# Auto2017.net
KiCad netlist of a schematic drawn in EAGLE
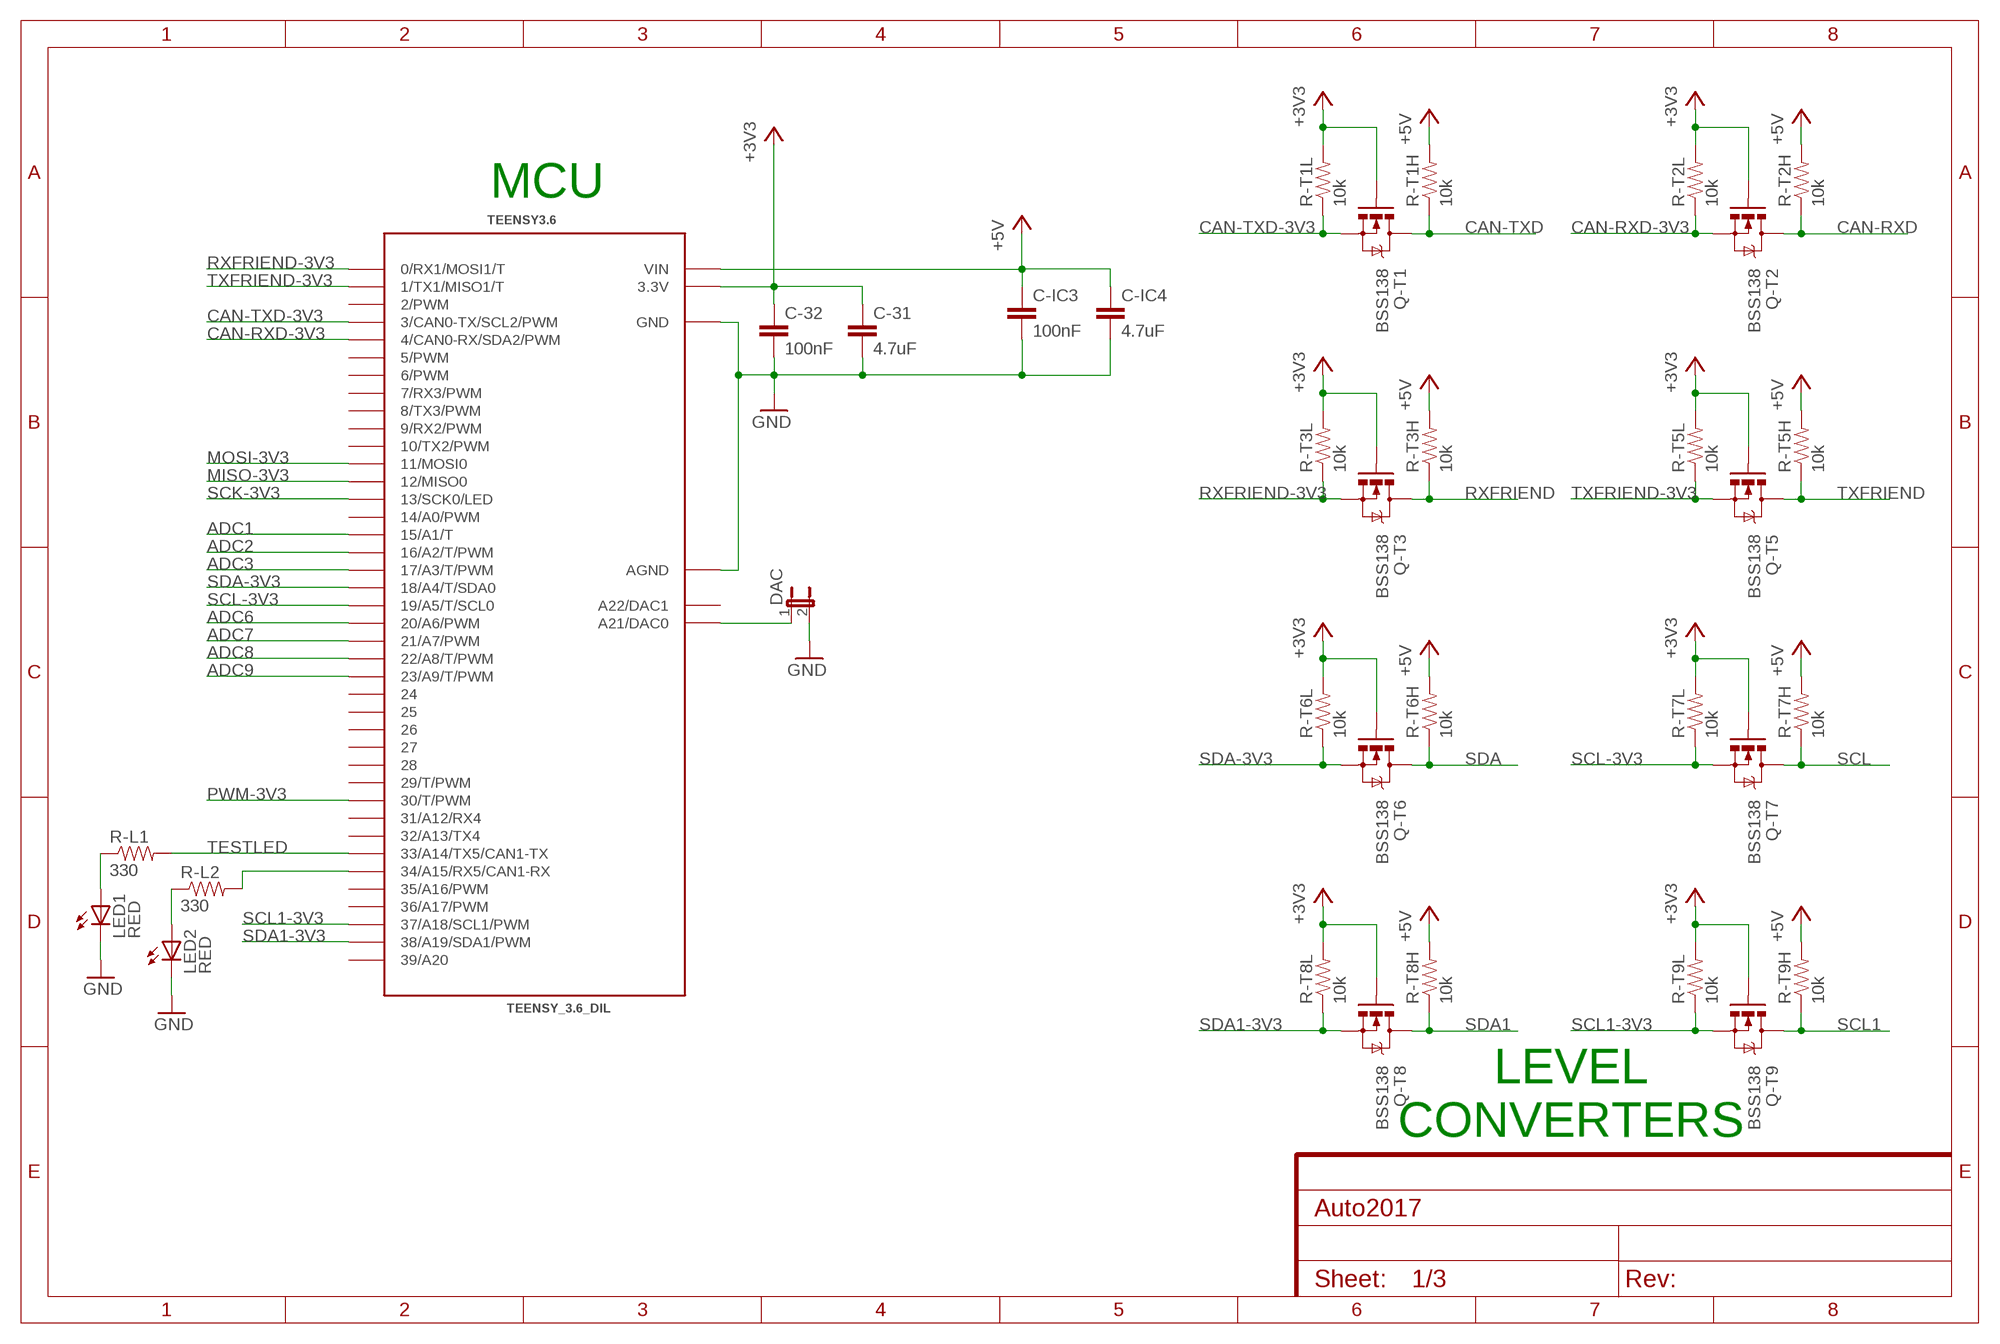
[diagram p0: schematic, sheet 1]
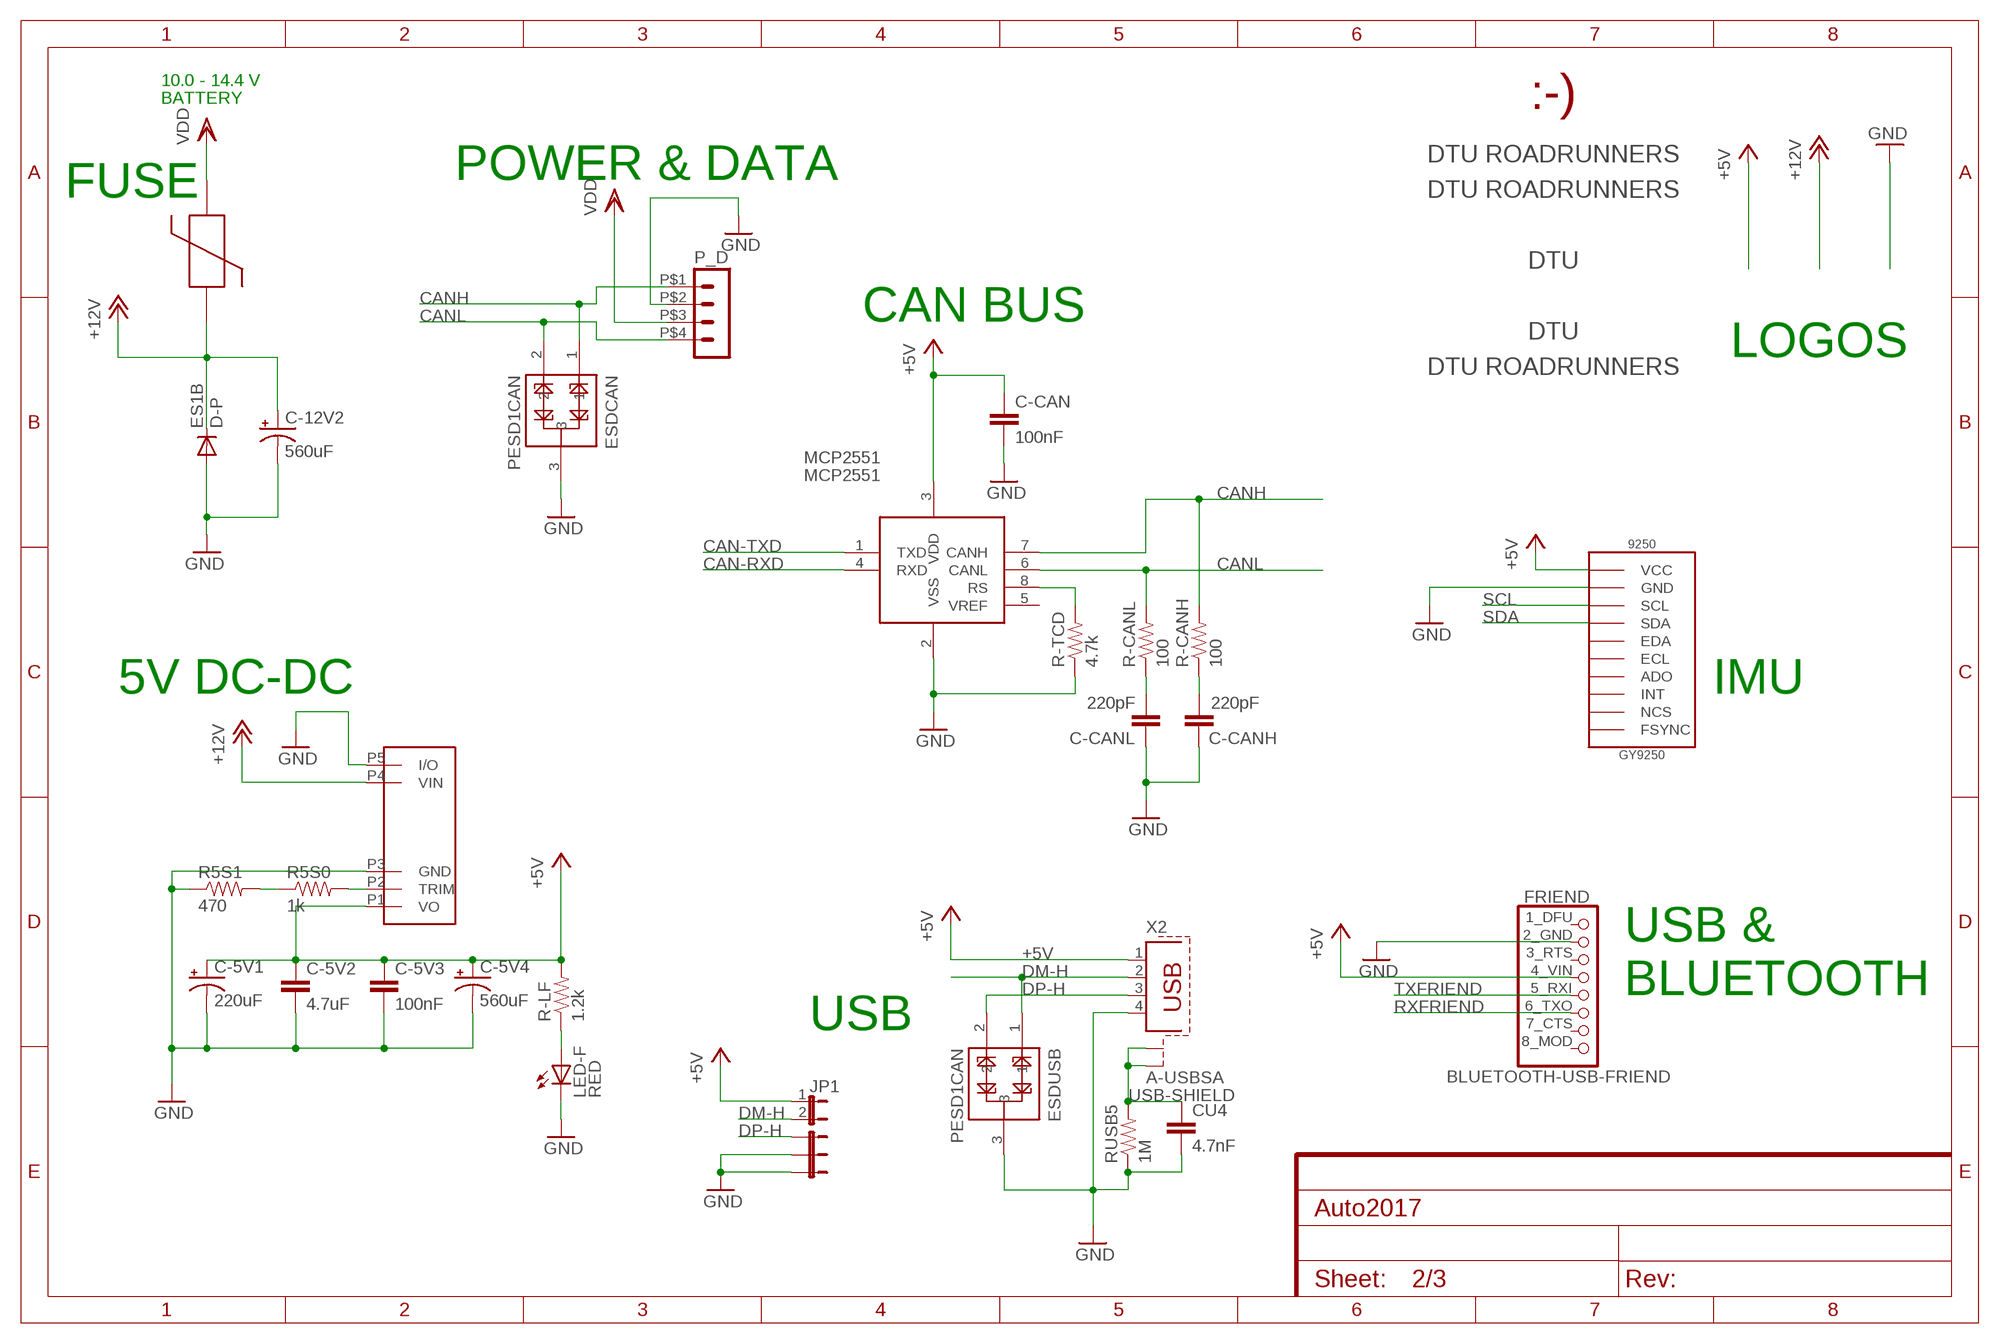
[diagram p1: schematic, sheet 2]
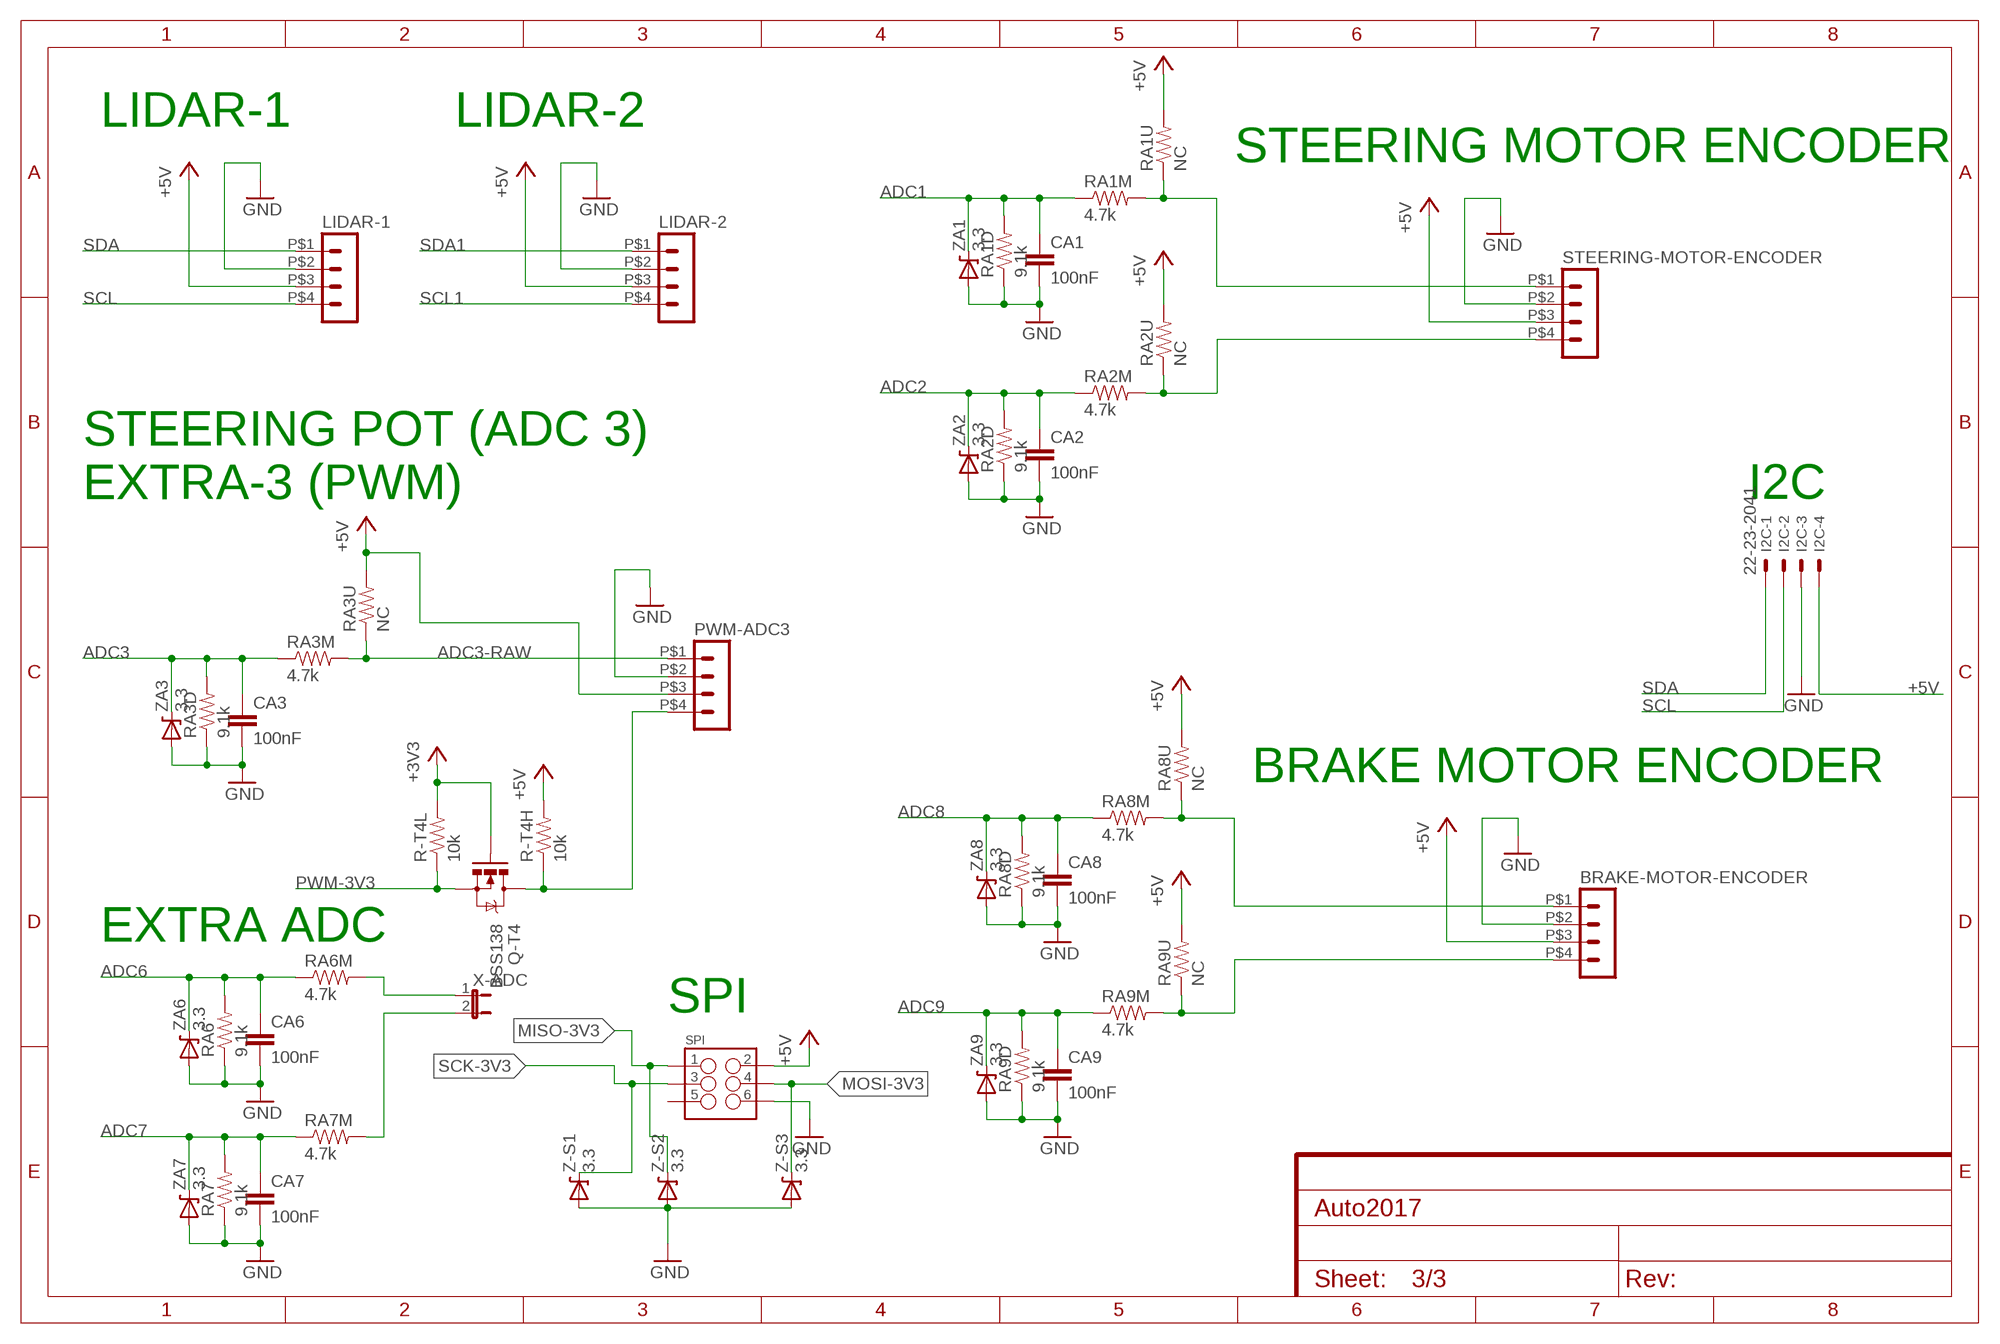
[diagram p2: schematic, sheet 3]

(export (version "E")
  (design (tool "Eeschema 10.0.6"))
  (components
    (comp (ref "BRAKE-MOTOR-ENCODER")
      (value "HEADER_POS4_43045-0401")
      (footprint "eagle-import:43045-0400")
      (libsource (lib "eagle-import") (part "HEADER_POS4_?43045-0401"))
    )
    (comp (ref "CA1")
      (value "100nF")
      (footprint "eagle-import:0805")
      (libsource (lib "eagle-import") (part "CAP0805"))
    )
    (comp (ref "CA2")
      (value "100nF")
      (footprint "eagle-import:0805")
      (libsource (lib "eagle-import") (part "CAP0805"))
    )
    (comp (ref "CA3")
      (value "100nF")
      (footprint "eagle-import:0805")
      (libsource (lib "eagle-import") (part "CAP0805"))
    )
    (comp (ref "CA6")
      (value "100nF")
      (footprint "eagle-import:0805")
      (libsource (lib "eagle-import") (part "CAP0805"))
    )
    (comp (ref "CA7")
      (value "100nF")
      (footprint "eagle-import:0805")
      (libsource (lib "eagle-import") (part "CAP0805"))
    )
    (comp (ref "CA8")
      (value "100nF")
      (footprint "eagle-import:0805")
      (libsource (lib "eagle-import") (part "CAP0805"))
    )
    (comp (ref "CA9")
      (value "100nF")
      (footprint "eagle-import:0805")
      (libsource (lib "eagle-import") (part "CAP0805"))
    )
    (comp (ref "I2C")
      (value "22-23-2041")
      (footprint "eagle-import:22-23-2041")
      (fields (field (name "MF") "MOLEX"))
      (libsource (lib "eagle-import") (part "22-23-2041"))
    )
    (comp (ref "LIDAR-1")
      (value "HEADER_POS4_43045-0401")
      (footprint "eagle-import:43045-0400")
      (libsource (lib "eagle-import") (part "HEADER_POS4_?43045-0401"))
    )
    (comp (ref "LIDAR-2")
      (value "HEADER_POS4_43045-0401")
      (footprint "eagle-import:43045-0400")
      (libsource (lib "eagle-import") (part "HEADER_POS4_?43045-0401"))
    )
    (comp (ref "PWM-ADC3")
      (value "HEADER_POS4_43045-0401")
      (footprint "eagle-import:43045-0400")
      (libsource (lib "eagle-import") (part "HEADER_POS4_?43045-0401"))
    )
    (comp (ref "Q-T4")
      (value "BSS138")
      (footprint "eagle-import:SOT23-3")
      (libsource (lib "eagle-import") (part "MOSFET-NCHANNELBSS123LT1G"))
    )
    (comp (ref "R-T4H")
      (value "10k")
      (footprint "eagle-import:0805")
      (libsource (lib "eagle-import") (part "RESISTOR0805-RES"))
    )
    (comp (ref "R-T4L")
      (value "10k")
      (footprint "eagle-import:0805")
      (libsource (lib "eagle-import") (part "RESISTOR0805-RES"))
    )
    (comp (ref "RA1D")
      (value "9.1k")
      (footprint "eagle-import:0805")
      (libsource (lib "eagle-import") (part "RESISTOR0805-RES"))
    )
    (comp (ref "RA1M")
      (value "4.7k")
      (footprint "eagle-import:0805")
      (libsource (lib "eagle-import") (part "RESISTOR0805-RES"))
    )
    (comp (ref "RA1U")
      (value "NC")
      (footprint "eagle-import:0805")
      (libsource (lib "eagle-import") (part "RESISTOR0805-RES"))
    )
    (comp (ref "RA2D")
      (value "9.1k")
      (footprint "eagle-import:0805")
      (libsource (lib "eagle-import") (part "RESISTOR0805-RES"))
    )
    (comp (ref "RA2M")
      (value "4.7k")
      (footprint "eagle-import:0805")
      (libsource (lib "eagle-import") (part "RESISTOR0805-RES"))
    )
    (comp (ref "RA2U")
      (value "NC")
      (footprint "eagle-import:0805")
      (libsource (lib "eagle-import") (part "RESISTOR0805-RES"))
    )
    (comp (ref "RA3D")
      (value "9.1k")
      (footprint "eagle-import:0805")
      (libsource (lib "eagle-import") (part "RESISTOR0805-RES"))
    )
    (comp (ref "RA3M")
      (value "4.7k")
      (footprint "eagle-import:0805")
      (libsource (lib "eagle-import") (part "RESISTOR0805-RES"))
    )
    (comp (ref "RA3U")
      (value "NC")
      (footprint "eagle-import:0805")
      (libsource (lib "eagle-import") (part "RESISTOR0805-RES"))
    )
    (comp (ref "RA6")
      (value "9.1k")
      (footprint "eagle-import:0805")
      (libsource (lib "eagle-import") (part "RESISTOR0805-RES"))
    )
    (comp (ref "RA6M")
      (value "4.7k")
      (footprint "eagle-import:0805")
      (libsource (lib "eagle-import") (part "RESISTOR0805-RES"))
    )
    (comp (ref "RA7")
      (value "9.1k")
      (footprint "eagle-import:0805")
      (libsource (lib "eagle-import") (part "RESISTOR0805-RES"))
    )
    (comp (ref "RA7M")
      (value "4.7k")
      (footprint "eagle-import:0805")
      (libsource (lib "eagle-import") (part "RESISTOR0805-RES"))
    )
    (comp (ref "RA8D")
      (value "9.1k")
      (footprint "eagle-import:0805")
      (libsource (lib "eagle-import") (part "RESISTOR0805-RES"))
    )
    (comp (ref "RA8M")
      (value "4.7k")
      (footprint "eagle-import:0805")
      (libsource (lib "eagle-import") (part "RESISTOR0805-RES"))
    )
    (comp (ref "RA8U")
      (value "NC")
      (footprint "eagle-import:0805")
      (libsource (lib "eagle-import") (part "RESISTOR0805-RES"))
    )
    (comp (ref "RA9D")
      (value "9.1k")
      (footprint "eagle-import:0805")
      (libsource (lib "eagle-import") (part "RESISTOR0805-RES"))
    )
    (comp (ref "RA9M")
      (value "4.7k")
      (footprint "eagle-import:0805")
      (libsource (lib "eagle-import") (part "RESISTOR0805-RES"))
    )
    (comp (ref "RA9U")
      (value "NC")
      (footprint "eagle-import:0805")
      (libsource (lib "eagle-import") (part "RESISTOR0805-RES"))
    )
    (comp (ref "SPI")
      (value "M03X2POGO_PINS")
      (footprint "eagle-import:2X3_POGO")
      (libsource (lib "eagle-import") (part "M03X2POGO_PINS"))
    )
    (comp (ref "STEERING-MOTOR-ENCODER")
      (value "HEADER_POS4_43045-0401")
      (footprint "eagle-import:43045-0400")
      (libsource (lib "eagle-import") (part "HEADER_POS4_?43045-0401"))
    )
    (comp (ref "X-ADC")
      (value "JUMPER-2PTH")
      (footprint "eagle-import:1X02")
      (libsource (lib "eagle-import") (part "JUMPER-2PTH"))
    )
    (comp (ref "Z-S1")
      (value "3.3")
      (footprint "eagle-import:SOD123")
      (libsource (lib "eagle-import") (part "ZENER"))
    )
    (comp (ref "Z-S2")
      (value "3.3")
      (footprint "eagle-import:SOD123")
      (libsource (lib "eagle-import") (part "ZENER"))
    )
    (comp (ref "Z-S3")
      (value "3.3")
      (footprint "eagle-import:SOD123")
      (libsource (lib "eagle-import") (part "ZENER"))
    )
    (comp (ref "ZA1")
      (value "3.3")
      (footprint "eagle-import:SOD123")
      (libsource (lib "eagle-import") (part "ZENER"))
    )
    (comp (ref "ZA2")
      (value "3.3")
      (footprint "eagle-import:SOD123")
      (libsource (lib "eagle-import") (part "ZENER"))
    )
    (comp (ref "ZA3")
      (value "3.3")
      (footprint "eagle-import:SOD123")
      (libsource (lib "eagle-import") (part "ZENER"))
    )
    (comp (ref "ZA6")
      (value "3.3")
      (footprint "eagle-import:SOD123")
      (libsource (lib "eagle-import") (part "ZENER"))
    )
    (comp (ref "ZA7")
      (value "3.3")
      (footprint "eagle-import:SOD123")
      (libsource (lib "eagle-import") (part "ZENER"))
    )
    (comp (ref "ZA8")
      (value "3.3")
      (footprint "eagle-import:SOD123")
      (libsource (lib "eagle-import") (part "ZENER"))
    )
    (comp (ref "ZA9")
      (value "3.3")
      (footprint "eagle-import:SOD123")
      (libsource (lib "eagle-import") (part "ZENER"))
    )
    (comp (ref "C-31")
      (value "4.7uF")
      (footprint "eagle-import:1210")
      (libsource (lib "eagle-import") (part "CAP1210"))
    )
    (comp (ref "C-32")
      (value "100nF")
      (footprint "eagle-import:0805")
      (libsource (lib "eagle-import") (part "CAP0805"))
    )
    (comp (ref "C-IC3")
      (value "100nF")
      (footprint "eagle-import:0805")
      (libsource (lib "eagle-import") (part "CAP0805"))
    )
    (comp (ref "C-IC4")
      (value "4.7uF")
      (footprint "eagle-import:1210")
      (libsource (lib "eagle-import") (part "CAP1210"))
    )
    (comp (ref "DAC")
      (value "JUMPER-2PTH")
      (footprint "eagle-import:1X02")
      (libsource (lib "eagle-import") (part "JUMPER-2PTH"))
    )
    (comp (ref "LED1")
      (value "RED")
      (footprint "eagle-import:LED-1206")
      (libsource (lib "eagle-import") (part "LED1206"))
    )
    (comp (ref "LED2")
      (value "RED")
      (footprint "eagle-import:LED-1206")
      (libsource (lib "eagle-import") (part "LED1206"))
    )
    (comp (ref "Q-T1")
      (value "BSS138")
      (footprint "eagle-import:SOT23-3")
      (libsource (lib "eagle-import") (part "MOSFET-NCHANNELBSS123LT1G"))
    )
    (comp (ref "Q-T2")
      (value "BSS138")
      (footprint "eagle-import:SOT23-3")
      (libsource (lib "eagle-import") (part "MOSFET-NCHANNELBSS123LT1G"))
    )
    (comp (ref "Q-T3")
      (value "BSS138")
      (footprint "eagle-import:SOT23-3")
      (libsource (lib "eagle-import") (part "MOSFET-NCHANNELBSS123LT1G"))
    )
    (comp (ref "Q-T5")
      (value "BSS138")
      (footprint "eagle-import:SOT23-3")
      (libsource (lib "eagle-import") (part "MOSFET-NCHANNELBSS123LT1G"))
    )
    (comp (ref "Q-T6")
      (value "BSS138")
      (footprint "eagle-import:SOT23-3")
      (libsource (lib "eagle-import") (part "MOSFET-NCHANNELBSS123LT1G"))
    )
    (comp (ref "Q-T7")
      (value "BSS138")
      (footprint "eagle-import:SOT23-3")
      (libsource (lib "eagle-import") (part "MOSFET-NCHANNELBSS123LT1G"))
    )
    (comp (ref "Q-T8")
      (value "BSS138")
      (footprint "eagle-import:SOT23-3")
      (libsource (lib "eagle-import") (part "MOSFET-NCHANNELBSS123LT1G"))
    )
    (comp (ref "Q-T9")
      (value "BSS138")
      (footprint "eagle-import:SOT23-3")
      (libsource (lib "eagle-import") (part "MOSFET-NCHANNELBSS123LT1G"))
    )
    (comp (ref "R-L1")
      (value "330")
      (footprint "eagle-import:0805")
      (libsource (lib "eagle-import") (part "RESISTOR0805-RES"))
    )
    (comp (ref "R-L2")
      (value "330")
      (footprint "eagle-import:0805")
      (libsource (lib "eagle-import") (part "RESISTOR0805-RES"))
    )
    (comp (ref "R-T1H")
      (value "10k")
      (footprint "eagle-import:0805")
      (libsource (lib "eagle-import") (part "RESISTOR0805-RES"))
    )
    (comp (ref "R-T1L")
      (value "10k")
      (footprint "eagle-import:0805")
      (libsource (lib "eagle-import") (part "RESISTOR0805-RES"))
    )
    (comp (ref "R-T2H")
      (value "10k")
      (footprint "eagle-import:0805")
      (libsource (lib "eagle-import") (part "RESISTOR0805-RES"))
    )
    (comp (ref "R-T2L")
      (value "10k")
      (footprint "eagle-import:0805")
      (libsource (lib "eagle-import") (part "RESISTOR0805-RES"))
    )
    (comp (ref "R-T3H")
      (value "10k")
      (footprint "eagle-import:0805")
      (libsource (lib "eagle-import") (part "RESISTOR0805-RES"))
    )
    (comp (ref "R-T3L")
      (value "10k")
      (footprint "eagle-import:0805")
      (libsource (lib "eagle-import") (part "RESISTOR0805-RES"))
    )
    (comp (ref "R-T5H")
      (value "10k")
      (footprint "eagle-import:0805")
      (libsource (lib "eagle-import") (part "RESISTOR0805-RES"))
    )
    (comp (ref "R-T5L")
      (value "10k")
      (footprint "eagle-import:0805")
      (libsource (lib "eagle-import") (part "RESISTOR0805-RES"))
    )
    (comp (ref "R-T6H")
      (value "10k")
      (footprint "eagle-import:0805")
      (libsource (lib "eagle-import") (part "RESISTOR0805-RES"))
    )
    (comp (ref "R-T6L")
      (value "10k")
      (footprint "eagle-import:0805")
      (libsource (lib "eagle-import") (part "RESISTOR0805-RES"))
    )
    (comp (ref "R-T7H")
      (value "10k")
      (footprint "eagle-import:0805")
      (libsource (lib "eagle-import") (part "RESISTOR0805-RES"))
    )
    (comp (ref "R-T7L")
      (value "10k")
      (footprint "eagle-import:0805")
      (libsource (lib "eagle-import") (part "RESISTOR0805-RES"))
    )
    (comp (ref "R-T8H")
      (value "10k")
      (footprint "eagle-import:0805")
      (libsource (lib "eagle-import") (part "RESISTOR0805-RES"))
    )
    (comp (ref "R-T8L")
      (value "10k")
      (footprint "eagle-import:0805")
      (libsource (lib "eagle-import") (part "RESISTOR0805-RES"))
    )
    (comp (ref "R-T9H")
      (value "10k")
      (footprint "eagle-import:0805")
      (libsource (lib "eagle-import") (part "RESISTOR0805-RES"))
    )
    (comp (ref "R-T9L")
      (value "10k")
      (footprint "eagle-import:0805")
      (libsource (lib "eagle-import") (part "RESISTOR0805-RES"))
    )
    (comp (ref "TEENSY3.6")
      (value "TEENSY_3.6_DIL")
      (footprint "eagle-import:TEENSY_3.6_DIL")
      (libsource (lib "eagle-import") (part "TEENSY_3.6_DIL"))
    )
    (comp (ref "9250")
      (value "GY9250")
      (footprint "eagle-import:GY9250")
      (libsource (lib "eagle-import") (part "GY9250"))
    )
    (comp (ref "C-5V1")
      (value "220uF")
      (footprint "eagle-import:PANASONIC_D")
      (libsource (lib "eagle-import") (part "CPOL-USD"))
    )
    (comp (ref "C-5V2")
      (value "4.7uF")
      (footprint "eagle-import:1210")
      (libsource (lib "eagle-import") (part "CAP1210"))
    )
    (comp (ref "C-5V3")
      (value "100nF")
      (footprint "eagle-import:0805")
      (libsource (lib "eagle-import") (part "CAP0805"))
    )
    (comp (ref "C-5V4")
      (value "560uF")
      (footprint "eagle-import:PANASONIC_G")
      (libsource (lib "eagle-import") (part "CPOL-USG"))
    )
    (comp (ref "C-12V2")
      (value "560uF")
      (footprint "eagle-import:PANASONIC_G")
      (libsource (lib "eagle-import") (part "CPOL-USG"))
    )
    (comp (ref "C-CAN")
      (value "100nF")
      (footprint "eagle-import:0805")
      (libsource (lib "eagle-import") (part "CAP0805"))
    )
    (comp (ref "C-CANH")
      (value "220pF")
      (footprint "eagle-import:0805")
      (libsource (lib "eagle-import") (part "CAP0805"))
    )
    (comp (ref "C-CANL")
      (value "220pF")
      (footprint "eagle-import:0805")
      (libsource (lib "eagle-import") (part "CAP0805"))
    )
    (comp (ref "CU4")
      (value "4.7nF")
      (footprint "eagle-import:0805")
      (libsource (lib "eagle-import") (part "CAP0805"))
    )
    (comp (ref "D-P")
      (value "ES1B")
      (footprint "eagle-import:SMA-DIODE")
      (libsource (lib "eagle-import") (part "DIODESMA"))
    )
    (comp (ref "ESDCAN")
      (value "PESD1CAN")
      (footprint "eagle-import:SOT23-3")
      (libsource (lib "eagle-import") (part "PESD1CAN"))
    )
    (comp (ref "ESDUSB")
      (value "PESD1CAN")
      (footprint "eagle-import:SOT23-3")
      (libsource (lib "eagle-import") (part "PESD1CAN"))
    )
    (comp (ref "FRIEND")
      (value "BLUETOOTH-USB-FRIEND")
      (footprint "eagle-import:1X08_ROUND_76")
      (libsource (lib "eagle-import") (part "BLUETOOTH-USB-FRIEND"))
    )
    (comp (ref "JP1")
      (value "JUMPER-2PTH")
      (footprint "eagle-import:1X02")
      (libsource (lib "eagle-import") (part "JUMPER-2PTH"))
    )
    (comp (ref "JP3")
      (value "JUMPER-3PTH")
      (footprint "eagle-import:1X03")
      (libsource (lib "eagle-import") (part "JUMPER-3PTH"))
    )
    (comp (ref "LED-F")
      (value "RED")
      (footprint "eagle-import:LED-1206")
      (libsource (lib "eagle-import") (part "LED1206"))
    )
    (comp (ref "MAIN_FUSE")
      (value "SMF_OMNI-BLOK_FUSE_BLOCK")
      (footprint "eagle-import:SMF_OMNI-BLOK_FUSE_BLOCK")
      (libsource (lib "eagle-import") (part "SMF_OMNI-BLOK_FUSE_BLOCK"))
    )
    (comp (ref "MCP2551")
      (value "MCP2551")
      (footprint "eagle-import:SO-08M")
      (libsource (lib "eagle-import") (part "MCP2551"))
    )
    (comp (ref "P_D")
      (value "HEADER_POS4_43045-0401")
      (footprint "eagle-import:43045-0400")
      (libsource (lib "eagle-import") (part "HEADER_POS4_?43045-0401"))
    )
    (comp (ref "R-CANH")
      (value "100")
      (footprint "eagle-import:0805")
      (libsource (lib "eagle-import") (part "RESISTOR0805-RES"))
    )
    (comp (ref "R-CANL")
      (value "100")
      (footprint "eagle-import:0805")
      (libsource (lib "eagle-import") (part "RESISTOR0805-RES"))
    )
    (comp (ref "R-LF")
      (value "1.2k")
      (footprint "eagle-import:0805")
      (libsource (lib "eagle-import") (part "RESISTOR0805-RES"))
    )
    (comp (ref "R-TCD")
      (value "4.7k")
      (footprint "eagle-import:0805")
      (libsource (lib "eagle-import") (part "RESISTOR0805-RES"))
    )
    (comp (ref "R5S0")
      (value "1k")
      (footprint "eagle-import:0805")
      (libsource (lib "eagle-import") (part "RESISTOR0805-RES"))
    )
    (comp (ref "R5S1")
      (value "470")
      (footprint "eagle-import:0805")
      (libsource (lib "eagle-import") (part "RESISTOR0805-RES"))
    )
    (comp (ref "RUSB5")
      (value "1M")
      (footprint "eagle-import:0805")
      (libsource (lib "eagle-import") (part "RESISTOR0805-RES"))
    )
    (comp (ref "U$1")
      (value "AXA003A0XZ")
      (footprint "eagle-import:SIP")
      (libsource (lib "eagle-import") (part "AXA003A0XZ"))
    )
    (comp (ref "U$3")
      (value "DTUMEDIUM-9MM")
      (footprint "eagle-import:DTU-MEDIUM-9MM")
      (libsource (lib "eagle-import") (part "DTUMEDIUM-9MM"))
    )
    (comp (ref "U$4")
      (value "ROADRUNNERSFULL")
      (footprint "eagle-import:ROADRUNNERS-FULL")
      (libsource (lib "eagle-import") (part "ROADRUNNERSFULL"))
    )
    (comp (ref "U$5")
      (value "ROADRUNNERSSMALL")
      (footprint "eagle-import:ROADRUNNERS-SMALL")
      (libsource (lib "eagle-import") (part "ROADRUNNERSSMALL"))
    )
    (comp (ref "U$6")
      (value "SMILEY")
      (footprint "eagle-import:SMILEY")
      (libsource (lib "eagle-import") (part "SMILEY"))
    )
    (comp (ref "U$8")
      (value "DTUSMALL")
      (footprint "eagle-import:DTU-SMALL-5MM")
      (libsource (lib "eagle-import") (part "DTUSMALL"))
    )
    (comp (ref "U$9")
      (value "ROADRUNNERSFULL")
      (footprint "eagle-import:ROADRUNNERS-FULL")
      (libsource (lib "eagle-import") (part "ROADRUNNERSFULL"))
    )
    (comp (ref "X2")
      (value "A-USBSA")
      (footprint "eagle-import:USB-A")
      (libsource (lib "eagle-import") (part "A-USBSA"))
    )
  )
  (nets
    (net (code "1") (name "+3V3") (class "Default")
      (node (ref "C-31") (pin "1") (pinfunction "1_1") (pintype "passive"))
      (node (ref "C-32") (pin "1") (pinfunction "1_1") (pintype "passive"))
      (node (ref "Q-T1") (pin "1") (pinfunction "G_1") (pintype "passive"))
      (node (ref "Q-T2") (pin "1") (pinfunction "G_1") (pintype "passive"))
      (node (ref "Q-T3") (pin "1") (pinfunction "G_1") (pintype "passive"))
      (node (ref "Q-T4") (pin "1") (pinfunction "G_1") (pintype "passive"))
      (node (ref "Q-T5") (pin "1") (pinfunction "G_1") (pintype "passive"))
      (node (ref "Q-T6") (pin "1") (pinfunction "G_1") (pintype "passive"))
      (node (ref "Q-T7") (pin "1") (pinfunction "G_1") (pintype "passive"))
      (node (ref "Q-T8") (pin "1") (pinfunction "G_1") (pintype "passive"))
      (node (ref "Q-T9") (pin "1") (pinfunction "G_1") (pintype "passive"))
      (node (ref "R-T1L") (pin "2") (pinfunction "2_2") (pintype "passive"))
      (node (ref "R-T2L") (pin "2") (pinfunction "2_2") (pintype "passive"))
      (node (ref "R-T3L") (pin "2") (pinfunction "2_2") (pintype "passive"))
      (node (ref "R-T4L") (pin "2") (pinfunction "2_2") (pintype "passive"))
      (node (ref "R-T5L") (pin "2") (pinfunction "2_2") (pintype "passive"))
      (node (ref "R-T6L") (pin "2") (pinfunction "2_2") (pintype "passive"))
      (node (ref "R-T7L") (pin "2") (pinfunction "2_2") (pintype "passive"))
      (node (ref "R-T8L") (pin "2") (pinfunction "2_2") (pintype "passive"))
      (node (ref "R-T9L") (pin "2") (pinfunction "2_2") (pintype "passive"))
      (node (ref "TEENSY3.6") (pin "3.3V") (pinfunction "3.3V_3.3V") (pintype "power_in"))
      (node (ref "TEENSY3.6") (pin "3.3V3") (pinfunction "3.3V_3.3V3") (pintype "power_in"))
    )
    (net (code "2") (name "+5V") (class "Default")
      (node (ref "9250") (pin "P$VCC") (pinfunction "VCC_P$VCC") (pintype "bidirectional"))
      (node (ref "BRAKE-MOTOR-ENCODER") (pin "P$3") (pinfunction "3_P$3") (pintype "passive"))
      (node (ref "C-5V1") (pin "+") (pinfunction "+_+") (pintype "passive"))
      (node (ref "C-5V2") (pin "1") (pinfunction "1_1") (pintype "passive"))
      (node (ref "C-5V3") (pin "1") (pinfunction "1_1") (pintype "passive"))
      (node (ref "C-5V4") (pin "+") (pinfunction "+_+") (pintype "passive"))
      (node (ref "C-CAN") (pin "1") (pinfunction "1_1") (pintype "passive"))
      (node (ref "C-IC3") (pin "1") (pinfunction "1_1") (pintype "passive"))
      (node (ref "C-IC4") (pin "1") (pinfunction "1_1") (pintype "passive"))
      (node (ref "FRIEND") (pin "4_VIN") (pinfunction "4_4_VIN") (pintype "passive"))
      (node (ref "I2C") (pin "4") (pinfunction "S_4") (pintype "passive"))
      (node (ref "JP1") (pin "1") (pinfunction "1_1") (pintype "passive"))
      (node (ref "LIDAR-1") (pin "P$3") (pinfunction "3_P$3") (pintype "passive"))
      (node (ref "LIDAR-2") (pin "P$3") (pinfunction "3_P$3") (pintype "passive"))
      (node (ref "MCP2551") (pin "3") (pinfunction "VDD_3") (pintype "power_in"))
      (node (ref "PWM-ADC3") (pin "P$3") (pinfunction "3_P$3") (pintype "passive"))
      (node (ref "R-LF") (pin "2") (pinfunction "2_2") (pintype "passive"))
      (node (ref "R-T1H") (pin "2") (pinfunction "2_2") (pintype "passive"))
      (node (ref "R-T2H") (pin "2") (pinfunction "2_2") (pintype "passive"))
      (node (ref "R-T3H") (pin "2") (pinfunction "2_2") (pintype "passive"))
      (node (ref "R-T4H") (pin "2") (pinfunction "2_2") (pintype "passive"))
      (node (ref "R-T5H") (pin "2") (pinfunction "2_2") (pintype "passive"))
      (node (ref "R-T6H") (pin "2") (pinfunction "2_2") (pintype "passive"))
      (node (ref "R-T7H") (pin "2") (pinfunction "2_2") (pintype "passive"))
      (node (ref "R-T8H") (pin "2") (pinfunction "2_2") (pintype "passive"))
      (node (ref "R-T9H") (pin "2") (pinfunction "2_2") (pintype "passive"))
      (node (ref "RA1U") (pin "2") (pinfunction "2_2") (pintype "passive"))
      (node (ref "RA2U") (pin "2") (pinfunction "2_2") (pintype "passive"))
      (node (ref "RA3U") (pin "2") (pinfunction "2_2") (pintype "passive"))
      (node (ref "RA8U") (pin "2") (pinfunction "2_2") (pintype "passive"))
      (node (ref "RA9U") (pin "2") (pinfunction "2_2") (pintype "passive"))
      (node (ref "SPI") (pin "P$2") (pinfunction "2_P$2") (pintype "bidirectional"))
      (node (ref "STEERING-MOTOR-ENCODER") (pin "P$3") (pinfunction "3_P$3") (pintype "passive"))
      (node (ref "TEENSY3.6") (pin "VIN") (pinfunction "VIN_VIN") (pintype "power_in"))
      (node (ref "U$1") (pin "P1") (pinfunction "VO_P1") (pintype "bidirectional"))
      (node (ref "X2") (pin "1") (pinfunction "1_1") (pintype "passive"))
    )
    (net (code "3") (name "+12V") (class "Default")
      (node (ref "C-12V2") (pin "+") (pinfunction "+_+") (pintype "passive"))
      (node (ref "D-P") (pin "C") (pinfunction "C_C") (pintype "passive"))
      (node (ref "MAIN_FUSE") (pin "PIN1") (pinfunction "PIN1_PIN1") (pintype "bidirectional"))
      (node (ref "U$1") (pin "P4") (pinfunction "VIN_P4") (pintype "bidirectional"))
    )
    (net (code "4") (name "ADC1") (class "Default")
      (node (ref "CA1") (pin "1") (pinfunction "1_1") (pintype "passive"))
      (node (ref "RA1D") (pin "2") (pinfunction "2_2") (pintype "passive"))
      (node (ref "RA1M") (pin "1") (pinfunction "1_1") (pintype "passive"))
      (node (ref "TEENSY3.6") (pin "15/A1") (pinfunction "15/A1/T_15/A1") (pintype "bidirectional"))
      (node (ref "ZA1") (pin "C") (pinfunction "C_C") (pintype "passive"))
    )
    (net (code "5") (name "ADC2") (class "Default")
      (node (ref "CA2") (pin "1") (pinfunction "1_1") (pintype "passive"))
      (node (ref "RA2D") (pin "2") (pinfunction "2_2") (pintype "passive"))
      (node (ref "RA2M") (pin "1") (pinfunction "1_1") (pintype "passive"))
      (node (ref "TEENSY3.6") (pin "16/A2") (pinfunction "16/A2/T/PWM_16/A2") (pintype "bidirectional"))
      (node (ref "ZA2") (pin "C") (pinfunction "C_C") (pintype "passive"))
    )
    (net (code "6") (name "ADC3") (class "Default")
      (node (ref "CA3") (pin "1") (pinfunction "1_1") (pintype "passive"))
      (node (ref "RA3D") (pin "2") (pinfunction "2_2") (pintype "passive"))
      (node (ref "RA3M") (pin "1") (pinfunction "1_1") (pintype "passive"))
      (node (ref "TEENSY3.6") (pin "17/A3") (pinfunction "17/A3/T/PWM_17/A3") (pintype "bidirectional"))
      (node (ref "ZA3") (pin "C") (pinfunction "C_C") (pintype "passive"))
    )
    (net (code "7") (name "ADC3-RAW") (class "Default")
      (node (ref "PWM-ADC3") (pin "P$1") (pinfunction "1_P$1") (pintype "passive"))
      (node (ref "RA3M") (pin "2") (pinfunction "2_2") (pintype "passive"))
      (node (ref "RA3U") (pin "1") (pinfunction "1_1") (pintype "passive"))
    )
    (net (code "8") (name "ADC6") (class "Default")
      (node (ref "CA6") (pin "1") (pinfunction "1_1") (pintype "passive"))
      (node (ref "RA6") (pin "2") (pinfunction "2_2") (pintype "passive"))
      (node (ref "RA6M") (pin "1") (pinfunction "1_1") (pintype "passive"))
      (node (ref "TEENSY3.6") (pin "20/A6") (pinfunction "20/A6/PWM_20/A6") (pintype "bidirectional"))
      (node (ref "ZA6") (pin "C") (pinfunction "C_C") (pintype "passive"))
    )
    (net (code "9") (name "ADC7") (class "Default")
      (node (ref "CA7") (pin "1") (pinfunction "1_1") (pintype "passive"))
      (node (ref "RA7") (pin "2") (pinfunction "2_2") (pintype "passive"))
      (node (ref "RA7M") (pin "1") (pinfunction "1_1") (pintype "passive"))
      (node (ref "TEENSY3.6") (pin "21/A7") (pinfunction "21/A7/PWM_21/A7") (pintype "bidirectional"))
      (node (ref "ZA7") (pin "C") (pinfunction "C_C") (pintype "passive"))
    )
    (net (code "10") (name "ADC8") (class "Default")
      (node (ref "CA8") (pin "1") (pinfunction "1_1") (pintype "passive"))
      (node (ref "RA8D") (pin "2") (pinfunction "2_2") (pintype "passive"))
      (node (ref "RA8M") (pin "1") (pinfunction "1_1") (pintype "passive"))
      (node (ref "TEENSY3.6") (pin "22/A8") (pinfunction "22/A8/T/PWM_22/A8") (pintype "bidirectional"))
      (node (ref "ZA8") (pin "C") (pinfunction "C_C") (pintype "passive"))
    )
    (net (code "11") (name "ADC9") (class "Default")
      (node (ref "CA9") (pin "1") (pinfunction "1_1") (pintype "passive"))
      (node (ref "RA9D") (pin "2") (pinfunction "2_2") (pintype "passive"))
      (node (ref "RA9M") (pin "1") (pinfunction "1_1") (pintype "passive"))
      (node (ref "TEENSY3.6") (pin "23/A9") (pinfunction "23/A9/T/PWM_23/A9") (pintype "bidirectional"))
      (node (ref "ZA9") (pin "C") (pinfunction "C_C") (pintype "passive"))
    )
    (net (code "12") (name "CAN-RXD") (class "Default")
      (node (ref "MCP2551") (pin "4") (pinfunction "RXD_4") (pintype "bidirectional"))
      (node (ref "Q-T2") (pin "3") (pinfunction "D_3") (pintype "passive"))
      (node (ref "R-T2H") (pin "1") (pinfunction "1_1") (pintype "passive"))
    )
    (net (code "13") (name "CAN-RXD-3V3") (class "Default")
      (node (ref "Q-T2") (pin "2") (pinfunction "S_2") (pintype "passive"))
      (node (ref "R-T2L") (pin "1") (pinfunction "1_1") (pintype "passive"))
      (node (ref "TEENSY3.6") (pin "4") (pinfunction "4/CAN0-RX/SDA2/PWM_4") (pintype "bidirectional"))
    )
    (net (code "14") (name "CAN-TXD") (class "Default")
      (node (ref "MCP2551") (pin "1") (pinfunction "TXD_1") (pintype "bidirectional"))
      (node (ref "Q-T1") (pin "3") (pinfunction "D_3") (pintype "passive"))
      (node (ref "R-T1H") (pin "1") (pinfunction "1_1") (pintype "passive"))
    )
    (net (code "15") (name "CAN-TXD-3V3") (class "Default")
      (node (ref "Q-T1") (pin "2") (pinfunction "S_2") (pintype "passive"))
      (node (ref "R-T1L") (pin "1") (pinfunction "1_1") (pintype "passive"))
      (node (ref "TEENSY3.6") (pin "3") (pinfunction "3/CAN0-TX/SCL2/PWM_3") (pintype "bidirectional"))
    )
    (net (code "16") (name "CANH") (class "Default")
      (node (ref "ESDCAN") (pin "1") (pinfunction "1_1") (pintype "bidirectional"))
      (node (ref "MCP2551") (pin "7") (pinfunction "CANH_7") (pintype "bidirectional"))
      (node (ref "P_D") (pin "P$1") (pinfunction "1_P$1") (pintype "passive"))
      (node (ref "R-CANH") (pin "2") (pinfunction "2_2") (pintype "passive"))
    )
    (net (code "17") (name "CANL") (class "Default")
      (node (ref "ESDCAN") (pin "2") (pinfunction "2_2") (pintype "bidirectional"))
      (node (ref "MCP2551") (pin "6") (pinfunction "CANL_6") (pintype "bidirectional"))
      (node (ref "P_D") (pin "P$4") (pinfunction "4_P$4") (pintype "passive"))
      (node (ref "R-CANL") (pin "2") (pinfunction "2_2") (pintype "passive"))
    )
    (net (code "18") (name "DM-H") (class "Default")
      (node (ref "ESDUSB") (pin "1") (pinfunction "1_1") (pintype "bidirectional"))
      (node (ref "JP1") (pin "2") (pinfunction "2_2") (pintype "passive"))
      (node (ref "X2") (pin "2") (pinfunction "2_2") (pintype "passive"))
    )
    (net (code "19") (name "DP-H") (class "Default")
      (node (ref "ESDUSB") (pin "2") (pinfunction "2_2") (pintype "bidirectional"))
      (node (ref "JP3") (pin "1") (pinfunction "1_1") (pintype "passive"))
      (node (ref "X2") (pin "3") (pinfunction "3_3") (pintype "passive"))
    )
    (net (code "20") (name "GND") (class "Default")
      (node (ref "9250") (pin "P$GND") (pinfunction "GND_P$GND") (pintype "bidirectional"))
      (node (ref "BRAKE-MOTOR-ENCODER") (pin "P$2") (pinfunction "2_P$2") (pintype "passive"))
      (node (ref "C-12V2") (pin "-") (pinfunction "-_-") (pintype "passive"))
      (node (ref "C-31") (pin "2") (pinfunction "2_2") (pintype "passive"))
      (node (ref "C-32") (pin "2") (pinfunction "2_2") (pintype "passive"))
      (node (ref "C-5V1") (pin "-") (pinfunction "-_-") (pintype "passive"))
      (node (ref "C-5V2") (pin "2") (pinfunction "2_2") (pintype "passive"))
      (node (ref "C-5V3") (pin "2") (pinfunction "2_2") (pintype "passive"))
      (node (ref "C-5V4") (pin "-") (pinfunction "-_-") (pintype "passive"))
      (node (ref "C-CAN") (pin "2") (pinfunction "2_2") (pintype "passive"))
      (node (ref "C-CANH") (pin "1") (pinfunction "1_1") (pintype "passive"))
      (node (ref "C-CANL") (pin "1") (pinfunction "1_1") (pintype "passive"))
      (node (ref "C-IC3") (pin "2") (pinfunction "2_2") (pintype "passive"))
      (node (ref "C-IC4") (pin "2") (pinfunction "2_2") (pintype "passive"))
      (node (ref "CA1") (pin "2") (pinfunction "2_2") (pintype "passive"))
      (node (ref "CA2") (pin "2") (pinfunction "2_2") (pintype "passive"))
      (node (ref "CA3") (pin "2") (pinfunction "2_2") (pintype "passive"))
      (node (ref "CA6") (pin "2") (pinfunction "2_2") (pintype "passive"))
      (node (ref "CA7") (pin "2") (pinfunction "2_2") (pintype "passive"))
      (node (ref "CA8") (pin "2") (pinfunction "2_2") (pintype "passive"))
      (node (ref "CA9") (pin "2") (pinfunction "2_2") (pintype "passive"))
      (node (ref "CU4") (pin "2") (pinfunction "2_2") (pintype "passive"))
      (node (ref "D-P") (pin "A") (pinfunction "A_A") (pintype "passive"))
      (node (ref "DAC") (pin "2") (pinfunction "2_2") (pintype "passive"))
      (node (ref "ESDCAN") (pin "3") (pinfunction "3_3") (pintype "bidirectional"))
      (node (ref "ESDUSB") (pin "3") (pinfunction "3_3") (pintype "bidirectional"))
      (node (ref "FRIEND") (pin "2_GND") (pinfunction "2_2_GND") (pintype "passive"))
      (node (ref "I2C") (pin "3") (pinfunction "S_3") (pintype "passive"))
      (node (ref "JP3") (pin "2") (pinfunction "2_2") (pintype "passive"))
      (node (ref "JP3") (pin "3") (pinfunction "3_3") (pintype "passive"))
      (node (ref "LED-F") (pin "C") (pinfunction "C_C") (pintype "passive"))
      (node (ref "LED1") (pin "C") (pinfunction "C_C") (pintype "passive"))
      (node (ref "LED2") (pin "C") (pinfunction "C_C") (pintype "passive"))
      (node (ref "LIDAR-1") (pin "P$2") (pinfunction "2_P$2") (pintype "passive"))
      (node (ref "LIDAR-2") (pin "P$2") (pinfunction "2_P$2") (pintype "passive"))
      (node (ref "MCP2551") (pin "2") (pinfunction "VSS_2") (pintype "power_in"))
      (node (ref "PWM-ADC3") (pin "P$2") (pinfunction "2_P$2") (pintype "passive"))
      (node (ref "P_D") (pin "P$2") (pinfunction "2_P$2") (pintype "passive"))
      (node (ref "R-TCD") (pin "1") (pinfunction "1_1") (pintype "passive"))
      (node (ref "R5S1") (pin "1") (pinfunction "1_1") (pintype "passive"))
      (node (ref "RA1D") (pin "1") (pinfunction "1_1") (pintype "passive"))
      (node (ref "RA2D") (pin "1") (pinfunction "1_1") (pintype "passive"))
      (node (ref "RA3D") (pin "1") (pinfunction "1_1") (pintype "passive"))
      (node (ref "RA6") (pin "1") (pinfunction "1_1") (pintype "passive"))
      (node (ref "RA7") (pin "1") (pinfunction "1_1") (pintype "passive"))
      (node (ref "RA8D") (pin "1") (pinfunction "1_1") (pintype "passive"))
      (node (ref "RA9D") (pin "1") (pinfunction "1_1") (pintype "passive"))
      (node (ref "RUSB5") (pin "1") (pinfunction "1_1") (pintype "passive"))
      (node (ref "SPI") (pin "P$6") (pinfunction "6_P$6") (pintype "bidirectional"))
      (node (ref "STEERING-MOTOR-ENCODER") (pin "P$2") (pinfunction "2_P$2") (pintype "passive"))
      (node (ref "TEENSY3.6") (pin "AGND") (pinfunction "AGND_AGND") (pintype "power_in"))
      (node (ref "TEENSY3.6") (pin "GND") (pinfunction "GND_GND") (pintype "power_in"))
      (node (ref "TEENSY3.6") (pin "GND1") (pinfunction "GND_GND1") (pintype "power_in"))
      (node (ref "U$1") (pin "P3") (pinfunction "GND_P3") (pintype "bidirectional"))
      (node (ref "U$1") (pin "P5") (pinfunction "I/O_P5") (pintype "bidirectional"))
      (node (ref "X2") (pin "4") (pinfunction "4_4") (pintype "passive"))
      (node (ref "Z-S1") (pin "A") (pinfunction "A_A") (pintype "passive"))
      (node (ref "Z-S2") (pin "A") (pinfunction "A_A") (pintype "passive"))
      (node (ref "Z-S3") (pin "A") (pinfunction "A_A") (pintype "passive"))
      (node (ref "ZA1") (pin "A") (pinfunction "A_A") (pintype "passive"))
      (node (ref "ZA2") (pin "A") (pinfunction "A_A") (pintype "passive"))
      (node (ref "ZA3") (pin "A") (pinfunction "A_A") (pintype "passive"))
      (node (ref "ZA6") (pin "A") (pinfunction "A_A") (pintype "passive"))
      (node (ref "ZA7") (pin "A") (pinfunction "A_A") (pintype "passive"))
      (node (ref "ZA8") (pin "A") (pinfunction "A_A") (pintype "passive"))
      (node (ref "ZA9") (pin "A") (pinfunction "A_A") (pintype "passive"))
    )
    (net (code "21") (name "MISO-3V3") (class "Default")
      (node (ref "SPI") (pin "P$1") (pinfunction "1_P$1") (pintype "bidirectional"))
      (node (ref "TEENSY3.6") (pin "12") (pinfunction "12/MISO0_12") (pintype "bidirectional"))
      (node (ref "Z-S2") (pin "C") (pinfunction "C_C") (pintype "passive"))
    )
    (net (code "22") (name "MOSI-3V3") (class "Default")
      (node (ref "SPI") (pin "P$4") (pinfunction "4_P$4") (pintype "bidirectional"))
      (node (ref "TEENSY3.6") (pin "11") (pinfunction "11/MOSI0_11") (pintype "bidirectional"))
      (node (ref "Z-S3") (pin "C") (pinfunction "C_C") (pintype "passive"))
    )
    (net (code "23") (name "Net-(BRAKE-MOTOR-ENCODER-1)") (class "Default")
      (node (ref "BRAKE-MOTOR-ENCODER") (pin "P$1") (pinfunction "1_P$1") (pintype "passive"))
      (node (ref "RA8M") (pin "2") (pinfunction "2_2") (pintype "passive"))
      (node (ref "RA8U") (pin "1") (pinfunction "1_1") (pintype "passive"))
    )
    (net (code "24") (name "Net-(BRAKE-MOTOR-ENCODER-4)") (class "Default")
      (node (ref "BRAKE-MOTOR-ENCODER") (pin "P$4") (pinfunction "4_P$4") (pintype "passive"))
      (node (ref "RA9M") (pin "2") (pinfunction "2_2") (pintype "passive"))
      (node (ref "RA9U") (pin "1") (pinfunction "1_1") (pintype "passive"))
    )
    (net (code "25") (name "Net-(C-CANH-Pad2)") (class "Default")
      (node (ref "C-CANH") (pin "2") (pinfunction "2_2") (pintype "passive"))
      (node (ref "R-CANH") (pin "1") (pinfunction "1_1") (pintype "passive"))
    )
    (net (code "26") (name "Net-(C-CANL-Pad2)") (class "Default")
      (node (ref "C-CANL") (pin "2") (pinfunction "2_2") (pintype "passive"))
      (node (ref "R-CANL") (pin "1") (pinfunction "1_1") (pintype "passive"))
    )
    (net (code "27") (name "Net-(LED-F-PadA)") (class "Default")
      (node (ref "LED-F") (pin "A") (pinfunction "A_A") (pintype "passive"))
      (node (ref "R-LF") (pin "1") (pinfunction "1_1") (pintype "passive"))
    )
    (net (code "28") (name "Net-(LED1-PadA)") (class "Default")
      (node (ref "LED1") (pin "A") (pinfunction "A_A") (pintype "passive"))
      (node (ref "R-L1") (pin "1") (pinfunction "1_1") (pintype "passive"))
    )
    (net (code "29") (name "Net-(LED2-PadA)") (class "Default")
      (node (ref "LED2") (pin "A") (pinfunction "A_A") (pintype "passive"))
      (node (ref "R-L2") (pin "1") (pinfunction "1_1") (pintype "passive"))
    )
    (net (code "30") (name "Net-(MCP2551-RS)") (class "Default")
      (node (ref "MCP2551") (pin "8") (pinfunction "RS_8") (pintype "bidirectional"))
      (node (ref "R-TCD") (pin "2") (pinfunction "2_2") (pintype "passive"))
    )
    (net (code "31") (name "Net-(PWM-ADC3-4)") (class "Default")
      (node (ref "PWM-ADC3") (pin "P$4") (pinfunction "4_P$4") (pintype "passive"))
      (node (ref "Q-T4") (pin "3") (pinfunction "D_3") (pintype "passive"))
      (node (ref "R-T4H") (pin "1") (pinfunction "1_1") (pintype "passive"))
    )
    (net (code "32") (name "Net-(R5S0-Pad1)") (class "Default")
      (node (ref "R5S0") (pin "1") (pinfunction "1_1") (pintype "passive"))
      (node (ref "R5S1") (pin "2") (pinfunction "2_2") (pintype "passive"))
    )
    (net (code "33") (name "Net-(RA6M-Pad2)") (class "Default")
      (node (ref "RA6M") (pin "2") (pinfunction "2_2") (pintype "passive"))
      (node (ref "X-ADC") (pin "1") (pinfunction "1_1") (pintype "passive"))
    )
    (net (code "34") (name "Net-(RA7M-Pad2)") (class "Default")
      (node (ref "RA7M") (pin "2") (pinfunction "2_2") (pintype "passive"))
      (node (ref "X-ADC") (pin "2") (pinfunction "2_2") (pintype "passive"))
    )
    (net (code "35") (name "Net-(STEERING-MOTOR-ENCODER-1)") (class "Default")
      (node (ref "RA1M") (pin "2") (pinfunction "2_2") (pintype "passive"))
      (node (ref "RA1U") (pin "1") (pinfunction "1_1") (pintype "passive"))
      (node (ref "STEERING-MOTOR-ENCODER") (pin "P$1") (pinfunction "1_P$1") (pintype "passive"))
    )
    (net (code "36") (name "Net-(STEERING-MOTOR-ENCODER-4)") (class "Default")
      (node (ref "RA2M") (pin "2") (pinfunction "2_2") (pintype "passive"))
      (node (ref "RA2U") (pin "1") (pinfunction "1_1") (pintype "passive"))
      (node (ref "STEERING-MOTOR-ENCODER") (pin "P$4") (pinfunction "4_P$4") (pintype "passive"))
    )
    (net (code "37") (name "Net-(TEENSY3.6-34{slash}A15{slash}RX5{slash}CAN1-RX)") (class "Default")
      (node (ref "R-L2") (pin "2") (pinfunction "2_2") (pintype "passive"))
      (node (ref "TEENSY3.6") (pin "34/A15") (pinfunction "34/A15/RX5/CAN1-RX_34/A15") (pintype "bidirectional"))
    )
    (net (code "38") (name "Net-(TEENSY3.6-A21{slash}DAC0)") (class "Default")
      (node (ref "DAC") (pin "1") (pinfunction "1_1") (pintype "passive"))
      (node (ref "TEENSY3.6") (pin "A21") (pinfunction "A21/DAC0_A21") (pintype "bidirectional"))
    )
    (net (code "39") (name "Net-(U$1-TRIM)") (class "Default")
      (node (ref "R5S0") (pin "2") (pinfunction "2_2") (pintype "passive"))
      (node (ref "U$1") (pin "P2") (pinfunction "TRIM_P2") (pintype "bidirectional"))
    )
    (net (code "40") (name "PWM-3V3") (class "Default")
      (node (ref "Q-T4") (pin "2") (pinfunction "S_2") (pintype "passive"))
      (node (ref "R-T4L") (pin "1") (pinfunction "1_1") (pintype "passive"))
      (node (ref "TEENSY3.6") (pin "30") (pinfunction "30/T/PWM_30") (pintype "bidirectional"))
    )
    (net (code "41") (name "RXFRIEND") (class "Default")
      (node (ref "FRIEND") (pin "6_TXO") (pinfunction "6_6_TXO") (pintype "passive"))
      (node (ref "Q-T3") (pin "3") (pinfunction "D_3") (pintype "passive"))
      (node (ref "R-T3H") (pin "1") (pinfunction "1_1") (pintype "passive"))
    )
    (net (code "42") (name "RXFRIEND-3V3") (class "Default")
      (node (ref "Q-T3") (pin "2") (pinfunction "S_2") (pintype "passive"))
      (node (ref "R-T3L") (pin "1") (pinfunction "1_1") (pintype "passive"))
      (node (ref "TEENSY3.6") (pin "0") (pinfunction "0/RX1/MOSI1/T_0") (pintype "bidirectional"))
    )
    (net (code "43") (name "SCK-3V3") (class "Default")
      (node (ref "SPI") (pin "P$3") (pinfunction "3_P$3") (pintype "bidirectional"))
      (node (ref "TEENSY3.6") (pin "13") (pinfunction "13/SCK0/LED_13") (pintype "bidirectional"))
      (node (ref "Z-S1") (pin "C") (pinfunction "C_C") (pintype "passive"))
    )
    (net (code "44") (name "SCL") (class "Default")
      (node (ref "9250") (pin "P$SCL") (pinfunction "SCL_P$SCL") (pintype "bidirectional"))
      (node (ref "I2C") (pin "2") (pinfunction "S_2") (pintype "passive"))
      (node (ref "LIDAR-1") (pin "P$4") (pinfunction "4_P$4") (pintype "passive"))
      (node (ref "Q-T7") (pin "3") (pinfunction "D_3") (pintype "passive"))
      (node (ref "R-T7H") (pin "1") (pinfunction "1_1") (pintype "passive"))
    )
    (net (code "45") (name "SCL-3V3") (class "Default")
      (node (ref "Q-T7") (pin "2") (pinfunction "S_2") (pintype "passive"))
      (node (ref "R-T7L") (pin "1") (pinfunction "1_1") (pintype "passive"))
      (node (ref "TEENSY3.6") (pin "19/A5") (pinfunction "19/A5/T/SCL0_19/A5") (pintype "bidirectional"))
    )
    (net (code "46") (name "SCL1") (class "Default")
      (node (ref "LIDAR-2") (pin "P$4") (pinfunction "4_P$4") (pintype "passive"))
      (node (ref "Q-T9") (pin "3") (pinfunction "D_3") (pintype "passive"))
      (node (ref "R-T9H") (pin "1") (pinfunction "1_1") (pintype "passive"))
    )
    (net (code "47") (name "SCL1-3V3") (class "Default")
      (node (ref "Q-T9") (pin "2") (pinfunction "S_2") (pintype "passive"))
      (node (ref "R-T9L") (pin "1") (pinfunction "1_1") (pintype "passive"))
      (node (ref "TEENSY3.6") (pin "37/A18") (pinfunction "37/A18/SCL1/PWM_37/A18") (pintype "bidirectional"))
    )
    (net (code "48") (name "SDA") (class "Default")
      (node (ref "9250") (pin "P$SDA") (pinfunction "SDA_P$SDA") (pintype "bidirectional"))
      (node (ref "I2C") (pin "1") (pinfunction "S_1") (pintype "passive"))
      (node (ref "LIDAR-1") (pin "P$1") (pinfunction "1_P$1") (pintype "passive"))
      (node (ref "Q-T6") (pin "3") (pinfunction "D_3") (pintype "passive"))
      (node (ref "R-T6H") (pin "1") (pinfunction "1_1") (pintype "passive"))
    )
    (net (code "49") (name "SDA-3V3") (class "Default")
      (node (ref "Q-T6") (pin "2") (pinfunction "S_2") (pintype "passive"))
      (node (ref "R-T6L") (pin "1") (pinfunction "1_1") (pintype "passive"))
      (node (ref "TEENSY3.6") (pin "18/A4") (pinfunction "18/A4/T/SDA0_18/A4") (pintype "bidirectional"))
    )
    (net (code "50") (name "SDA1") (class "Default")
      (node (ref "LIDAR-2") (pin "P$1") (pinfunction "1_P$1") (pintype "passive"))
      (node (ref "Q-T8") (pin "3") (pinfunction "D_3") (pintype "passive"))
      (node (ref "R-T8H") (pin "1") (pinfunction "1_1") (pintype "passive"))
    )
    (net (code "51") (name "SDA1-3V3") (class "Default")
      (node (ref "Q-T8") (pin "2") (pinfunction "S_2") (pintype "passive"))
      (node (ref "R-T8L") (pin "1") (pinfunction "1_1") (pintype "passive"))
      (node (ref "TEENSY3.6") (pin "38/A19") (pinfunction "38/A19/SDA1/PWM_38/A19") (pintype "bidirectional"))
    )
    (net (code "52") (name "TESTLED") (class "Default")
      (node (ref "R-L1") (pin "2") (pinfunction "2_2") (pintype "passive"))
      (node (ref "TEENSY3.6") (pin "33/A14") (pinfunction "33/A14/TX5/CAN1-TX_33/A14") (pintype "bidirectional"))
    )
    (net (code "53") (name "TXFRIEND") (class "Default")
      (node (ref "FRIEND") (pin "5_RXI") (pinfunction "5_5_RXI") (pintype "passive"))
      (node (ref "Q-T5") (pin "3") (pinfunction "D_3") (pintype "passive"))
      (node (ref "R-T5H") (pin "1") (pinfunction "1_1") (pintype "passive"))
    )
    (net (code "54") (name "TXFRIEND-3V3") (class "Default")
      (node (ref "Q-T5") (pin "2") (pinfunction "S_2") (pintype "passive"))
      (node (ref "R-T5L") (pin "1") (pinfunction "1_1") (pintype "passive"))
      (node (ref "TEENSY3.6") (pin "1") (pinfunction "1/TX1/MISO1/T_1") (pintype "bidirectional"))
    )
    (net (code "55") (name "USB-SHIELD") (class "Default")
      (node (ref "CU4") (pin "1") (pinfunction "1_1") (pintype "passive"))
      (node (ref "RUSB5") (pin "2") (pinfunction "2_2") (pintype "passive"))
      (node (ref "X2") (pin "S1") (pinfunction "S1_S1") (pintype "passive"))
      (node (ref "X2") (pin "S2") (pinfunction "S2_S2") (pintype "passive"))
    )
    (net (code "56") (name "VDD") (class "Default")
      (node (ref "MAIN_FUSE") (pin "PIN2") (pinfunction "PIN2_PIN2") (pintype "bidirectional"))
      (node (ref "P_D") (pin "P$3") (pinfunction "3_P$3") (pintype "passive"))
    )
    (net (code "57") (name "unconnected-(9250-ADO-PadP$ADO)") (class "Default")
      (node (ref "9250") (pin "P$ADO") (pinfunction "ADO_P$ADO") (pintype "bidirectional"))
    )
    (net (code "58") (name "unconnected-(9250-ECL-PadP$ECL)") (class "Default")
      (node (ref "9250") (pin "P$ECL") (pinfunction "ECL_P$ECL") (pintype "bidirectional"))
    )
    (net (code "59") (name "unconnected-(9250-EDA-PadP$EDA)") (class "Default")
      (node (ref "9250") (pin "P$EDA") (pinfunction "EDA_P$EDA") (pintype "bidirectional"))
    )
    (net (code "60") (name "unconnected-(9250-FSYNC-PadP$FSYNC)") (class "Default")
      (node (ref "9250") (pin "P$FSYNC") (pinfunction "FSYNC_P$FSYNC") (pintype "bidirectional"))
    )
    (net (code "61") (name "unconnected-(9250-INT-PadP$INT)") (class "Default")
      (node (ref "9250") (pin "P$INT") (pinfunction "INT_P$INT") (pintype "bidirectional"))
    )
    (net (code "62") (name "unconnected-(9250-NCS-PadP$NCS)") (class "Default")
      (node (ref "9250") (pin "P$NCS") (pinfunction "NCS_P$NCS") (pintype "bidirectional"))
    )
    (net (code "63") (name "unconnected-(FRIEND-1-Pad1_DFU)") (class "Default")
      (node (ref "FRIEND") (pin "1_DFU") (pinfunction "1_1_DFU") (pintype "passive"))
    )
    (net (code "64") (name "unconnected-(FRIEND-3-Pad3_RTS)") (class "Default")
      (node (ref "FRIEND") (pin "3_RTS") (pinfunction "3_3_RTS") (pintype "passive"))
    )
    (net (code "65") (name "unconnected-(FRIEND-7-Pad7_CTS)") (class "Default")
      (node (ref "FRIEND") (pin "7_CTS") (pinfunction "7_7_CTS") (pintype "passive"))
    )
    (net (code "66") (name "unconnected-(FRIEND-8-Pad8_MOD)") (class "Default")
      (node (ref "FRIEND") (pin "8_MOD") (pinfunction "8_8_MOD") (pintype "passive"))
    )
    (net (code "67") (name "unconnected-(MCP2551-VREF-Pad5)") (class "Default")
      (node (ref "MCP2551") (pin "5") (pinfunction "VREF_5") (pintype "bidirectional"))
    )
    (net (code "68") (name "unconnected-(SPI-5-PadP$5)") (class "Default")
      (node (ref "SPI") (pin "P$5") (pinfunction "5_P$5") (pintype "bidirectional"))
    )
    (net (code "69") (name "unconnected-(TEENSY3.6-2{slash}PWM-Pad2)") (class "Default")
      (node (ref "TEENSY3.6") (pin "2") (pinfunction "2/PWM_2") (pintype "bidirectional"))
    )
    (net (code "70") (name "unconnected-(TEENSY3.6-5{slash}PWM-Pad5)") (class "Default")
      (node (ref "TEENSY3.6") (pin "5") (pinfunction "5/PWM_5") (pintype "bidirectional"))
    )
    (net (code "71") (name "unconnected-(TEENSY3.6-6{slash}PWM-Pad6)") (class "Default")
      (node (ref "TEENSY3.6") (pin "6") (pinfunction "6/PWM_6") (pintype "bidirectional"))
    )
    (net (code "72") (name "unconnected-(TEENSY3.6-7{slash}RX3{slash}PWM-Pad7)") (class "Default")
      (node (ref "TEENSY3.6") (pin "7") (pinfunction "7/RX3/PWM_7") (pintype "bidirectional"))
    )
    (net (code "73") (name "unconnected-(TEENSY3.6-8{slash}TX3{slash}PWM-Pad8)") (class "Default")
      (node (ref "TEENSY3.6") (pin "8") (pinfunction "8/TX3/PWM_8") (pintype "bidirectional"))
    )
    (net (code "74") (name "unconnected-(TEENSY3.6-9{slash}RX2{slash}PWM-Pad9)") (class "Default")
      (node (ref "TEENSY3.6") (pin "9") (pinfunction "9/RX2/PWM_9") (pintype "bidirectional"))
    )
    (net (code "75") (name "unconnected-(TEENSY3.6-10{slash}TX2{slash}PWM-Pad10)") (class "Default")
      (node (ref "TEENSY3.6") (pin "10") (pinfunction "10/TX2/PWM_10") (pintype "bidirectional"))
    )
    (net (code "76") (name "unconnected-(TEENSY3.6-14{slash}A0{slash}PWM-Pad14{slash}A0)") (class "Default")
      (node (ref "TEENSY3.6") (pin "14/A0") (pinfunction "14/A0/PWM_14/A0") (pintype "bidirectional"))
    )
    (net (code "77") (name "unconnected-(TEENSY3.6-29{slash}T{slash}PWM-Pad29)") (class "Default")
      (node (ref "TEENSY3.6") (pin "29") (pinfunction "29/T/PWM_29") (pintype "bidirectional"))
    )
    (net (code "78") (name "unconnected-(TEENSY3.6-31{slash}A12{slash}RX4-Pad31{slash}A12)") (class "Default")
      (node (ref "TEENSY3.6") (pin "31/A12") (pinfunction "31/A12/RX4_31/A12") (pintype "bidirectional"))
    )
    (net (code "79") (name "unconnected-(TEENSY3.6-32{slash}A13{slash}TX4-Pad32{slash}A13)") (class "Default")
      (node (ref "TEENSY3.6") (pin "32/A13") (pinfunction "32/A13/TX4_32/A13") (pintype "bidirectional"))
    )
    (net (code "80") (name "unconnected-(TEENSY3.6-35{slash}A16{slash}PWM-Pad35{slash}A16)") (class "Default")
      (node (ref "TEENSY3.6") (pin "35/A16") (pinfunction "35/A16/PWM_35/A16") (pintype "bidirectional"))
    )
    (net (code "81") (name "unconnected-(TEENSY3.6-36{slash}A17{slash}PWM-Pad36{slash}A17)") (class "Default")
      (node (ref "TEENSY3.6") (pin "36/A17") (pinfunction "36/A17/PWM_36/A17") (pintype "bidirectional"))
    )
    (net (code "82") (name "unconnected-(TEENSY3.6-A22{slash}DAC1-PadA22)") (class "Default")
      (node (ref "TEENSY3.6") (pin "A22") (pinfunction "A22/DAC1_A22") (pintype "bidirectional"))
    )
    (net (code "83") (name "unconnected-(TEENSY3.6-Pad24)") (class "Default")
      (node (ref "TEENSY3.6") (pin "24") (pinfunction "24_24") (pintype "bidirectional"))
    )
    (net (code "84") (name "unconnected-(TEENSY3.6-Pad25)") (class "Default")
      (node (ref "TEENSY3.6") (pin "25") (pinfunction "25_25") (pintype "bidirectional"))
    )
    (net (code "85") (name "unconnected-(TEENSY3.6-Pad26)") (class "Default")
      (node (ref "TEENSY3.6") (pin "26") (pinfunction "26_26") (pintype "bidirectional"))
    )
    (net (code "86") (name "unconnected-(TEENSY3.6-Pad27)") (class "Default")
      (node (ref "TEENSY3.6") (pin "27") (pinfunction "27_27") (pintype "bidirectional"))
    )
    (net (code "87") (name "unconnected-(TEENSY3.6-Pad28)") (class "Default")
      (node (ref "TEENSY3.6") (pin "28") (pinfunction "28_28") (pintype "bidirectional"))
    )
    (net (code "88") (name "unconnected-(TEENSY3.6-Pad39{slash}A20)") (class "Default")
      (node (ref "TEENSY3.6") (pin "39/A20") (pinfunction "39/A20_39/A20") (pintype "bidirectional"))
    )
  )
)
